# Charging_TI.net
KiCad netlist of a schematic drawn in Altium Designer
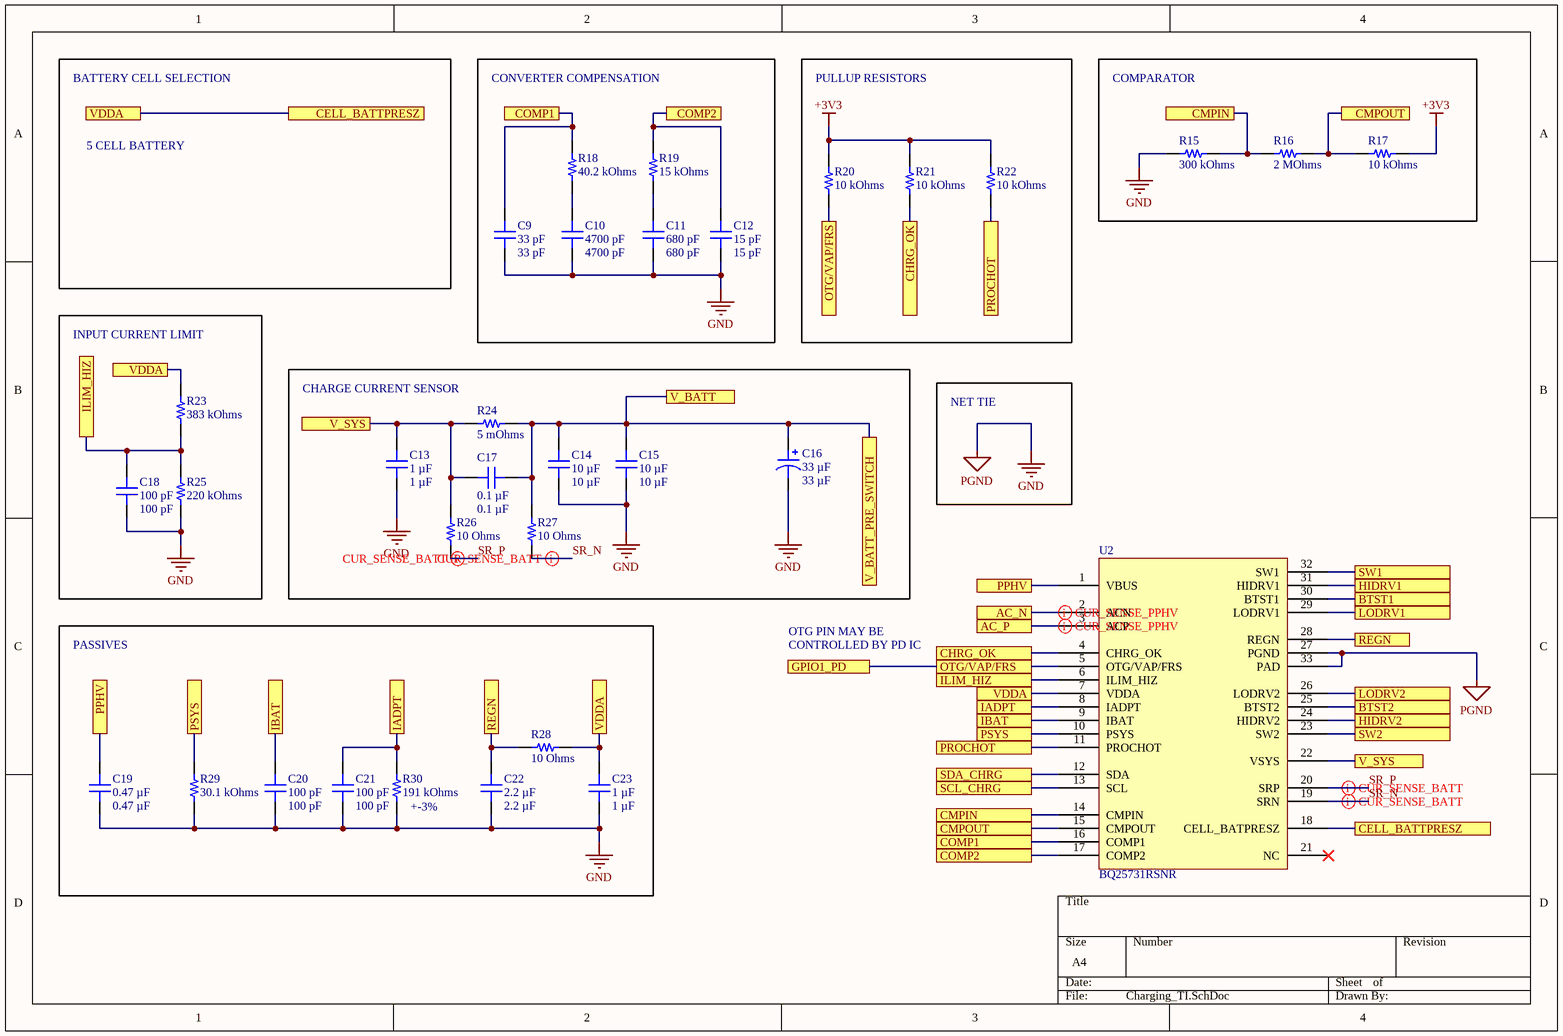
[diagram p0: Charging_TI.SchDoc]

(export (version "E")
  (design (tool "Eeschema 10.0.6"))
  (components
    (comp (ref "C9")
      (value "33 pF")
      (footprint "CAP 0402_1005")
      (description "CAP CER 33PF 50V CH 0402")
      (fields
        (field (name "PART NUMBER") "UMK105CH330JVHF")
        (field (name "ALTIUM_VALUE") "33 pF")
        (field (name "MANUFACTURER") "Taiyo Yuden")
      )
      (libsource (lib "Celestial Altium Library - altium_library") (part "Capacitor"))
    )
    (comp (ref "C10")
      (value "4700 pF")
      (footprint "CAP 0402_1005")
      (description "CAP CER 4700PF 50V X7R 0402")
      (fields
        (field (name "PART NUMBER") "0402B472J500CT")
        (field (name "ALTIUM_VALUE") "4700 pF")
        (field (name "MANUFACTURER") "Walsin Technology Corporation")
      )
      (libsource (lib "Celestial Altium Library - altium_library") (part "Capacitor"))
    )
    (comp (ref "C11")
      (value "680 pF")
      (footprint "CAP 0402_1005")
      (description "CAP CER 680PF 50V NP0 0402")
      (fields
        (field (name "PART NUMBER") "C1005NP01H681J050BA")
        (field (name "ALTIUM_VALUE") "680 pF")
        (field (name "MANUFACTURER") "TDK Corporation")
      )
      (libsource (lib "Celestial Altium Library - altium_library") (part "Capacitor"))
    )
    (comp (ref "C12")
      (value "15 pF")
      (footprint "CAP 0402_1005")
      (description "CAP CER 15PF 50V C0G/NP0 0402")
      (fields
        (field (name "PART NUMBER") "CBR04C150J5GAC")
        (field (name "ALTIUM_VALUE") "15 pF")
        (field (name "MANUFACTURER") "KEMET")
      )
      (libsource (lib "Celestial Altium Library - altium_library") (part "Capacitor"))
    )
    (comp (ref "C13")
      (value "1 µF")
      (footprint "CAP 0402_1005")
      (description "CAP CER 1UF 16V X5R 0402")
      (fields
        (field (name "PART NUMBER") "EMK105BJ105MV-F")
        (field (name "ALTIUM_VALUE") "1 µF")
        (field (name "MANUFACTURER") "Taiyo Yuden")
      )
      (libsource (lib "Celestial Altium Library - altium_library") (part "Capacitor"))
    )
    (comp (ref "C14")
      (value "10 µF")
      (footprint "CAP 0805_2012")
      (description "CAP CER 10UF 50V X5R 0805")
      (fields
        (field (name "PART NUMBER") "GRM21BR61H106KE43L")
        (field (name "ALTIUM_VALUE") "10 µF")
        (field (name "MANUFACTURER") "Murata Electronics")
      )
      (libsource (lib "Celestial Altium Library - altium_library") (part "Capacitor"))
    )
    (comp (ref "C15")
      (value "10 µF")
      (footprint "CAP 0805_2012")
      (description "CAP CER 10UF 50V X5R 0805")
      (fields
        (field (name "PART NUMBER") "GRM21BR61H106KE43L")
        (field (name "ALTIUM_VALUE") "10 µF")
        (field (name "MANUFACTURER") "Murata Electronics")
      )
      (libsource (lib "Celestial Altium Library - altium_library") (part "Capacitor"))
    )
    (comp (ref "C16")
      (value "33 µF")
      (footprint "CAP POL 2917_7343")
      (description "CAP TANT 33UF 20% 35V 2917")
      (fields
        (field (name "PART NUMBER") "T495X336M035ATE175")
        (field (name "ALTIUM_VALUE") "33 µF")
        (field (name "MANUFACTURER") "KEMET")
      )
      (libsource (lib "Celestial Altium Library - altium_library") (part "Polarised Capacitor"))
    )
    (comp (ref "C17")
      (value "0.1 µF")
      (footprint "CAP 0603_1608")
      (description "CAP CER 0.1UF 50V X7R 0603")
      (fields
        (field (name "PART NUMBER") "C0603C104K5RAC7411")
        (field (name "ALTIUM_VALUE") "0.1 µF")
        (field (name "MANUFACTURER") "KEMET")
      )
      (libsource (lib "Celestial Altium Library - altium_library") (part "Capacitor"))
    )
    (comp (ref "C18")
      (value "100 pF")
      (footprint "CAP 0603_1608")
      (description "CAP CER 100PF 50V C0G/NP0 0603")
      (fields
        (field (name "PART NUMBER") "C0603C101K5GACAUTO")
        (field (name "ALTIUM_VALUE") "100 pF")
        (field (name "MANUFACTURER") "KEMET")
      )
      (libsource (lib "Celestial Altium Library - altium_library") (part "Capacitor"))
    )
    (comp (ref "C19")
      (value "0.47 µF")
      (footprint "CAP 0805_2012")
      (description "CAP CER 0.47UF 50V X7R 0805")
      (fields
        (field (name "PART NUMBER") "C0805C474K5RACAUTO")
        (field (name "ALTIUM_VALUE") "0.47 µF")
        (field (name "MANUFACTURER") "KEMET")
      )
      (libsource (lib "Celestial Altium Library - altium_library") (part "Capacitor"))
    )
    (comp (ref "C20")
      (value "100 pF")
      (footprint "CAP 0603_1608")
      (description "CAP CER 100PF 50V C0G/NP0 0603")
      (fields
        (field (name "PART NUMBER") "C0603C101K5GACAUTO")
        (field (name "ALTIUM_VALUE") "100 pF")
        (field (name "MANUFACTURER") "KEMET")
      )
      (libsource (lib "Celestial Altium Library - altium_library") (part "Capacitor"))
    )
    (comp (ref "C21")
      (value "100 pF")
      (footprint "CAP 0603_1608")
      (description "CAP CER 100PF 50V C0G/NP0 0603")
      (fields
        (field (name "PART NUMBER") "C0603C101K5GACAUTO")
        (field (name "ALTIUM_VALUE") "100 pF")
        (field (name "MANUFACTURER") "KEMET")
      )
      (libsource (lib "Celestial Altium Library - altium_library") (part "Capacitor"))
    )
    (comp (ref "C22")
      (value "2.2 µF")
      (footprint "CAP 0603_1608")
      (description "CAP CER 2.2UF 35V X5R 0603")
      (fields
        (field (name "PART NUMBER") "GRM188R6YA225KA12D")
        (field (name "ALTIUM_VALUE") "2.2 µF")
        (field (name "MANUFACTURER") "Murata Electronics")
      )
      (libsource (lib "Celestial Altium Library - altium_library") (part "Capacitor"))
    )
    (comp (ref "C23")
      (value "1 µF")
      (footprint "CAP 0603_1608")
      (description "CAP CER 1UF 35V X7R 0603")
      (fields
        (field (name "PART NUMBER") "GMJ107CB7105KAHR")
        (field (name "ALTIUM_VALUE") "1 µF")
        (field (name "MANUFACTURER") "Taiyo Yuden")
      )
      (libsource (lib "Celestial Altium Library - altium_library") (part "Capacitor"))
    )
    (comp (ref "R15")
      (value "300 kOhms")
      (footprint "RES 0402_1005")
      (description "RES 300K OHM 1% 1/16W 0402")
      (fields (field (name "PART NUMBER") "RC0402FR-07300KL") (field (name "MANUFACTURER") "Yageo"))
      (libsource (lib "Celestial Altium Library - altium_library") (part "Resistor"))
    )
    (comp (ref "R16")
      (value "2 MOhms")
      (footprint "RES 0402_1005")
      (description "RES 2M OHM 5% 1/16W 0402")
      (fields
        (field (name "PART NUMBER") "RMCF0402JT2M00")
        (field (name "MANUFACTURER") "Stackpole Electronics Inc")
      )
      (libsource (lib "Celestial Altium Library - altium_library") (part "Resistor"))
    )
    (comp (ref "R17")
      (value "10 kOhms")
      (footprint "RES 0402_1005")
      (description "RES 10K OHM 5% 1/16W 0402")
      (fields (field (name "PART NUMBER") "RC0402JR-1310KL") (field (name "MANUFACTURER") "Yageo"))
      (libsource (lib "Celestial Altium Library - altium_library") (part "Resistor"))
    )
    (comp (ref "R18")
      (value "40.2 kOhms")
      (footprint "RES 0402_1005")
      (description "RES 40.2K OHM 1% 1/16W 0402")
      (fields (field (name "PART NUMBER") "RC0402FR-0740K2L") (field (name "MANUFACTURER") "Yageo"))
      (libsource (lib "Celestial Altium Library - altium_library") (part "Resistor"))
    )
    (comp (ref "R19")
      (value "15 kOhms")
      (footprint "RES 0402_1005")
      (description "RES 15K OHM 1% 1/16W 0402")
      (fields (field (name "PART NUMBER") "RC0402FR-1315KL") (field (name "MANUFACTURER") "Yageo"))
      (libsource (lib "Celestial Altium Library - altium_library") (part "Resistor"))
    )
    (comp (ref "R20")
      (value "10 kOhms")
      (footprint "RES 0402_1005")
      (description "RES 10K OHM 5% 1/16W 0402")
      (fields (field (name "PART NUMBER") "RC0402JR-1310KL") (field (name "MANUFACTURER") "Yageo"))
      (libsource (lib "Celestial Altium Library - altium_library") (part "Resistor"))
    )
    (comp (ref "R21")
      (value "10 kOhms")
      (footprint "RES 0402_1005")
      (description "RES 10K OHM 5% 1/16W 0402")
      (fields (field (name "PART NUMBER") "RC0402JR-1310KL") (field (name "MANUFACTURER") "Yageo"))
      (libsource (lib "Celestial Altium Library - altium_library") (part "Resistor"))
    )
    (comp (ref "R22")
      (value "10 kOhms")
      (footprint "RES 0402_1005")
      (description "RES 10K OHM 5% 1/16W 0402")
      (fields (field (name "PART NUMBER") "RC0402JR-1310KL") (field (name "MANUFACTURER") "Yageo"))
      (libsource (lib "Celestial Altium Library - altium_library") (part "Resistor"))
    )
    (comp (ref "R23")
      (value "383 kOhms")
      (footprint "RES 0402_1005")
      (description "RES SMD 383K OHM 1% 1/10W 0402")
      (fields
        (field (name "PART NUMBER") "ERJ-2RKF3833X")
        (field (name "MANUFACTURER") "Panasonic Electronic Components")
      )
      (libsource (lib "Celestial Altium Library - altium_library") (part "Resistor"))
    )
    (comp (ref "R24")
      (value "5 mOhms")
      (footprint "RES 1206_3216")
      (description "RES 0.005 OHM 5% 1W 1206")
      (fields (field (name "PART NUMBER") "PMR18EZPJU5L0") (field (name "MANUFACTURER") "Rohm Semiconductor"))
      (libsource (lib "Celestial Altium Library - altium_library") (part "Resistor"))
    )
    (comp (ref "R25")
      (value "220 kOhms")
      (footprint "RES 0402_1005")
      (description "RES 220K OHM 1% 1/16W 0402")
      (fields (field (name "PART NUMBER") "RC0402FR-07220KL") (field (name "MANUFACTURER") "Yageo"))
      (libsource (lib "Celestial Altium Library - altium_library") (part "Resistor"))
    )
    (comp (ref "R26")
      (value "10 Ohms")
      (footprint "RES 0603_1608")
      (description "RES SMD 10 OHM 1% 1/10W 0603")
      (fields
        (field (name "PART NUMBER") "ERJ-3EKF10R0V")
        (field (name "MANUFACTURER") "Panasonic Electronic Components")
      )
      (libsource (lib "Celestial Altium Library - altium_library") (part "Resistor"))
    )
    (comp (ref "R27")
      (value "10 Ohms")
      (footprint "RES 0603_1608")
      (description "RES SMD 10 OHM 1% 1/10W 0603")
      (fields
        (field (name "PART NUMBER") "ERJ-3EKF10R0V")
        (field (name "MANUFACTURER") "Panasonic Electronic Components")
      )
      (libsource (lib "Celestial Altium Library - altium_library") (part "Resistor"))
    )
    (comp (ref "R28")
      (value "10 Ohms")
      (footprint "RES 0603_1608")
      (description "RES SMD 10 OHM 1% 1/10W 0603")
      (fields
        (field (name "PART NUMBER") "ERJ-3EKF10R0V")
        (field (name "MANUFACTURER") "Panasonic Electronic Components")
      )
      (libsource (lib "Celestial Altium Library - altium_library") (part "Resistor"))
    )
    (comp (ref "R29")
      (value "30.1 kOhms")
      (footprint "RES 0402_1005")
      (description "RES 30.1K OHM 1% 1/16W 0402")
      (fields (field (name "PART NUMBER") "RC0402FR-0730K1L") (field (name "MANUFACTURER") "Yageo"))
      (libsource (lib "Celestial Altium Library - altium_library") (part "Resistor"))
    )
    (comp (ref "R30")
      (value "191 kOhms")
      (footprint "RES 0402_1005")
      (description "RES SMD 191K OHM 1% 1/10W 0402")
      (fields
        (field (name "PART NUMBER") "ERJ-2RKF1913X")
        (field (name "MANUFACTURER") "Panasonic Electronic Components")
      )
      (libsource (lib "Celestial Altium Library - altium_library") (part "Resistor"))
    )
    (comp (ref "U2")
      (value "BQ25731RSNR")
      (footprint "QFN40P400X400X80_HS-33N")
      (description "I2C 1- to 5-Cell Buck-Boost Battery Charge Controller with USB-C PD 3.0 OTG Output")
      (libsource (lib "Schlib2") (part "BQ25731RSNR"))
    )
  )
  (nets
    (net (code "1") (name "+3V3") (class "Default")
      (node (ref "R17") (pin "1") (pinfunction "1_1") (pintype "passive"))
      (node (ref "R20") (pin "2") (pinfunction "2_2") (pintype "passive"))
      (node (ref "R21") (pin "2") (pinfunction "2_2") (pintype "passive"))
      (node (ref "R22") (pin "2") (pinfunction "2_2") (pintype "passive"))
    )
    (net (code "2") (name "/AC_N") (class "Default")
      (node (ref "U2") (pin "2") (pinfunction "ACN_2") (pintype "passive"))
    )
    (net (code "3") (name "/AC_P") (class "Default")
      (node (ref "U2") (pin "3") (pinfunction "ACP_3") (pintype "passive"))
    )
    (net (code "4") (name "/BTST1") (class "Default")
      (node (ref "U2") (pin "30") (pinfunction "BTST1_30") (pintype "passive"))
    )
    (net (code "5") (name "/BTST2") (class "Default")
      (node (ref "U2") (pin "25") (pinfunction "BTST2_25") (pintype "passive"))
    )
    (net (code "6") (name "/CELL_BATTPRESZ") (class "Default")
      (node (ref "C23") (pin "2") (pinfunction "2_2") (pintype "passive"))
      (node (ref "R23") (pin "2") (pinfunction "2_2") (pintype "passive"))
      (node (ref "R28") (pin "2") (pinfunction "2_2") (pintype "passive"))
      (node (ref "U2") (pin "18") (pinfunction "CELL_BATPRESZ_18") (pintype "passive"))
      (node (ref "U2") (pin "7") (pinfunction "VDDA_7") (pintype "passive"))
    )
    (net (code "7") (name "/CHRG_OK") (class "Default")
      (node (ref "R21") (pin "1") (pinfunction "1_1") (pintype "passive"))
      (node (ref "U2") (pin "4") (pinfunction "CHRG_OK_4") (pintype "passive"))
    )
    (net (code "8") (name "/CMPIN") (class "Default")
      (node (ref "R15") (pin "2") (pinfunction "2_2") (pintype "passive"))
      (node (ref "R16") (pin "1") (pinfunction "1_1") (pintype "passive"))
      (node (ref "U2") (pin "14") (pinfunction "CMPIN_14") (pintype "passive"))
    )
    (net (code "9") (name "/CMPOUT") (class "Default")
      (node (ref "R16") (pin "2") (pinfunction "2_2") (pintype "passive"))
      (node (ref "R17") (pin "2") (pinfunction "2_2") (pintype "passive"))
      (node (ref "U2") (pin "15") (pinfunction "CMPOUT_15") (pintype "passive"))
    )
    (net (code "10") (name "/COMP1") (class "Default")
      (node (ref "C9") (pin "2") (pinfunction "2_2") (pintype "passive"))
      (node (ref "R18") (pin "2") (pinfunction "2_2") (pintype "passive"))
      (node (ref "U2") (pin "16") (pinfunction "COMP1_16") (pintype "passive"))
    )
    (net (code "11") (name "/COMP2") (class "Default")
      (node (ref "C12") (pin "2") (pinfunction "2_2") (pintype "passive"))
      (node (ref "R19") (pin "2") (pinfunction "2_2") (pintype "passive"))
      (node (ref "U2") (pin "17") (pinfunction "COMP2_17") (pintype "passive"))
    )
    (net (code "12") (name "/GPIO1_PD") (class "Default")
      (node (ref "R20") (pin "1") (pinfunction "1_1") (pintype "passive"))
      (node (ref "U2") (pin "5") (pinfunction "OTG/VAP/FRS_5") (pintype "passive"))
    )
    (net (code "13") (name "/HIDRV1") (class "Default")
      (node (ref "U2") (pin "31") (pinfunction "HIDRV1_31") (pintype "passive"))
    )
    (net (code "14") (name "/HIDRV2") (class "Default")
      (node (ref "U2") (pin "24") (pinfunction "HIDRV2_24") (pintype "passive"))
    )
    (net (code "15") (name "/IADPT") (class "Default")
      (node (ref "C21") (pin "2") (pinfunction "2_2") (pintype "passive"))
      (node (ref "R30") (pin "2") (pinfunction "2_2") (pintype "passive"))
      (node (ref "U2") (pin "8") (pinfunction "IADPT_8") (pintype "passive"))
    )
    (net (code "16") (name "/IBAT") (class "Default")
      (node (ref "C20") (pin "2") (pinfunction "2_2") (pintype "passive"))
      (node (ref "U2") (pin "9") (pinfunction "IBAT_9") (pintype "passive"))
    )
    (net (code "17") (name "/ILIM_HIZ") (class "Default")
      (node (ref "C18") (pin "2") (pinfunction "2_2") (pintype "passive"))
      (node (ref "R23") (pin "1") (pinfunction "1_1") (pintype "passive"))
      (node (ref "R25") (pin "2") (pinfunction "2_2") (pintype "passive"))
      (node (ref "U2") (pin "6") (pinfunction "ILIM_HIZ_6") (pintype "passive"))
    )
    (net (code "18") (name "/LODRV1") (class "Default")
      (node (ref "U2") (pin "29") (pinfunction "LODRV1_29") (pintype "passive"))
    )
    (net (code "19") (name "/LODRV2") (class "Default")
      (node (ref "U2") (pin "26") (pinfunction "LODRV2_26") (pintype "passive"))
    )
    (net (code "20") (name "/PPHV") (class "Default")
      (node (ref "C19") (pin "2") (pinfunction "2_2") (pintype "passive"))
      (node (ref "U2") (pin "1") (pinfunction "VBUS_1") (pintype "passive"))
    )
    (net (code "21") (name "/PROCHOT") (class "Default")
      (node (ref "R22") (pin "1") (pinfunction "1_1") (pintype "passive"))
      (node (ref "U2") (pin "11") (pinfunction "PROCHOT_11") (pintype "passive"))
    )
    (net (code "22") (name "/PSYS") (class "Default")
      (node (ref "R29") (pin "2") (pinfunction "2_2") (pintype "passive"))
      (node (ref "U2") (pin "10") (pinfunction "PSYS_10") (pintype "passive"))
    )
    (net (code "23") (name "/REGN") (class "Default")
      (node (ref "C22") (pin "2") (pinfunction "2_2") (pintype "passive"))
      (node (ref "R28") (pin "1") (pinfunction "1_1") (pintype "passive"))
      (node (ref "U2") (pin "28") (pinfunction "REGN_28") (pintype "passive"))
    )
    (net (code "24") (name "/SCL_CHRG") (class "Default")
      (node (ref "U2") (pin "13") (pinfunction "SCL_13") (pintype "passive"))
    )
    (net (code "25") (name "/SDA_CHRG") (class "Default")
      (node (ref "U2") (pin "12") (pinfunction "SDA_12") (pintype "passive"))
    )
    (net (code "26") (name "/SR_N") (class "Default")
      (node (ref "R27") (pin "1") (pinfunction "1_1") (pintype "passive"))
      (node (ref "U2") (pin "19") (pinfunction "SRN_19") (pintype "passive"))
    )
    (net (code "27") (name "/SR_P") (class "Default")
      (node (ref "R26") (pin "1") (pinfunction "1_1") (pintype "passive"))
      (node (ref "U2") (pin "20") (pinfunction "SRP_20") (pintype "passive"))
    )
    (net (code "28") (name "/SW1") (class "Default")
      (node (ref "U2") (pin "32") (pinfunction "SW1_32") (pintype "passive"))
    )
    (net (code "29") (name "/SW2") (class "Default")
      (node (ref "U2") (pin "23") (pinfunction "SW2_23") (pintype "passive"))
    )
    (net (code "30") (name "/V_BATT") (class "Default")
      (node (ref "C14") (pin "2") (pinfunction "2_2") (pintype "passive"))
      (node (ref "C15") (pin "2") (pinfunction "2_2") (pintype "passive"))
      (node (ref "C16") (pin "1") (pinfunction "1_1") (pintype "passive"))
      (node (ref "C17") (pin "2") (pinfunction "2_2") (pintype "passive"))
      (node (ref "R24") (pin "2") (pinfunction "2_2") (pintype "passive"))
      (node (ref "R27") (pin "2") (pinfunction "2_2") (pintype "passive"))
    )
    (net (code "31") (name "/V_SYS") (class "Default")
      (node (ref "C13") (pin "1") (pinfunction "1_1") (pintype "passive"))
      (node (ref "C17") (pin "1") (pinfunction "1_1") (pintype "passive"))
      (node (ref "R24") (pin "1") (pinfunction "1_1") (pintype "passive"))
      (node (ref "R26") (pin "2") (pinfunction "2_2") (pintype "passive"))
      (node (ref "U2") (pin "22") (pinfunction "VSYS_22") (pintype "passive"))
    )
    (net (code "32") (name "GND") (class "Default")
      (node (ref "C10") (pin "1") (pinfunction "1_1") (pintype "passive"))
      (node (ref "C11") (pin "1") (pinfunction "1_1") (pintype "passive"))
      (node (ref "C12") (pin "1") (pinfunction "1_1") (pintype "passive"))
      (node (ref "C13") (pin "2") (pinfunction "2_2") (pintype "passive"))
      (node (ref "C14") (pin "1") (pinfunction "1_1") (pintype "passive"))
      (node (ref "C15") (pin "1") (pinfunction "1_1") (pintype "passive"))
      (node (ref "C16") (pin "2") (pinfunction "2_2") (pintype "passive"))
      (node (ref "C18") (pin "1") (pinfunction "1_1") (pintype "passive"))
      (node (ref "C19") (pin "1") (pinfunction "1_1") (pintype "passive"))
      (node (ref "C20") (pin "1") (pinfunction "1_1") (pintype "passive"))
      (node (ref "C21") (pin "1") (pinfunction "1_1") (pintype "passive"))
      (node (ref "C22") (pin "1") (pinfunction "1_1") (pintype "passive"))
      (node (ref "C23") (pin "1") (pinfunction "1_1") (pintype "passive"))
      (node (ref "C9") (pin "1") (pinfunction "1_1") (pintype "passive"))
      (node (ref "R15") (pin "1") (pinfunction "1_1") (pintype "passive"))
      (node (ref "R25") (pin "1") (pinfunction "1_1") (pintype "passive"))
      (node (ref "R29") (pin "1") (pinfunction "1_1") (pintype "passive"))
      (node (ref "R30") (pin "1") (pinfunction "1_1") (pintype "passive"))
      (node (ref "U2") (pin "27") (pinfunction "PGND_27") (pintype "passive"))
      (node (ref "U2") (pin "33") (pinfunction "PAD_33") (pintype "passive"))
    )
    (net (code "33") (name "Net-(C10-Pad2)") (class "Default")
      (node (ref "C10") (pin "2") (pinfunction "2_2") (pintype "passive"))
      (node (ref "R18") (pin "1") (pinfunction "1_1") (pintype "passive"))
    )
    (net (code "34") (name "Net-(C11-Pad2)") (class "Default")
      (node (ref "C11") (pin "2") (pinfunction "2_2") (pintype "passive"))
      (node (ref "R19") (pin "1") (pinfunction "1_1") (pintype "passive"))
    )
    (net (code "35") (name "unconnected-(U2-NC-Pad21)") (class "Default")
      (node (ref "U2") (pin "21") (pinfunction "NC_21") (pintype "passive+no_connect"))
    )
  )
)
